# LED_board.net
KiCad netlist of a schematic drawn in EAGLE
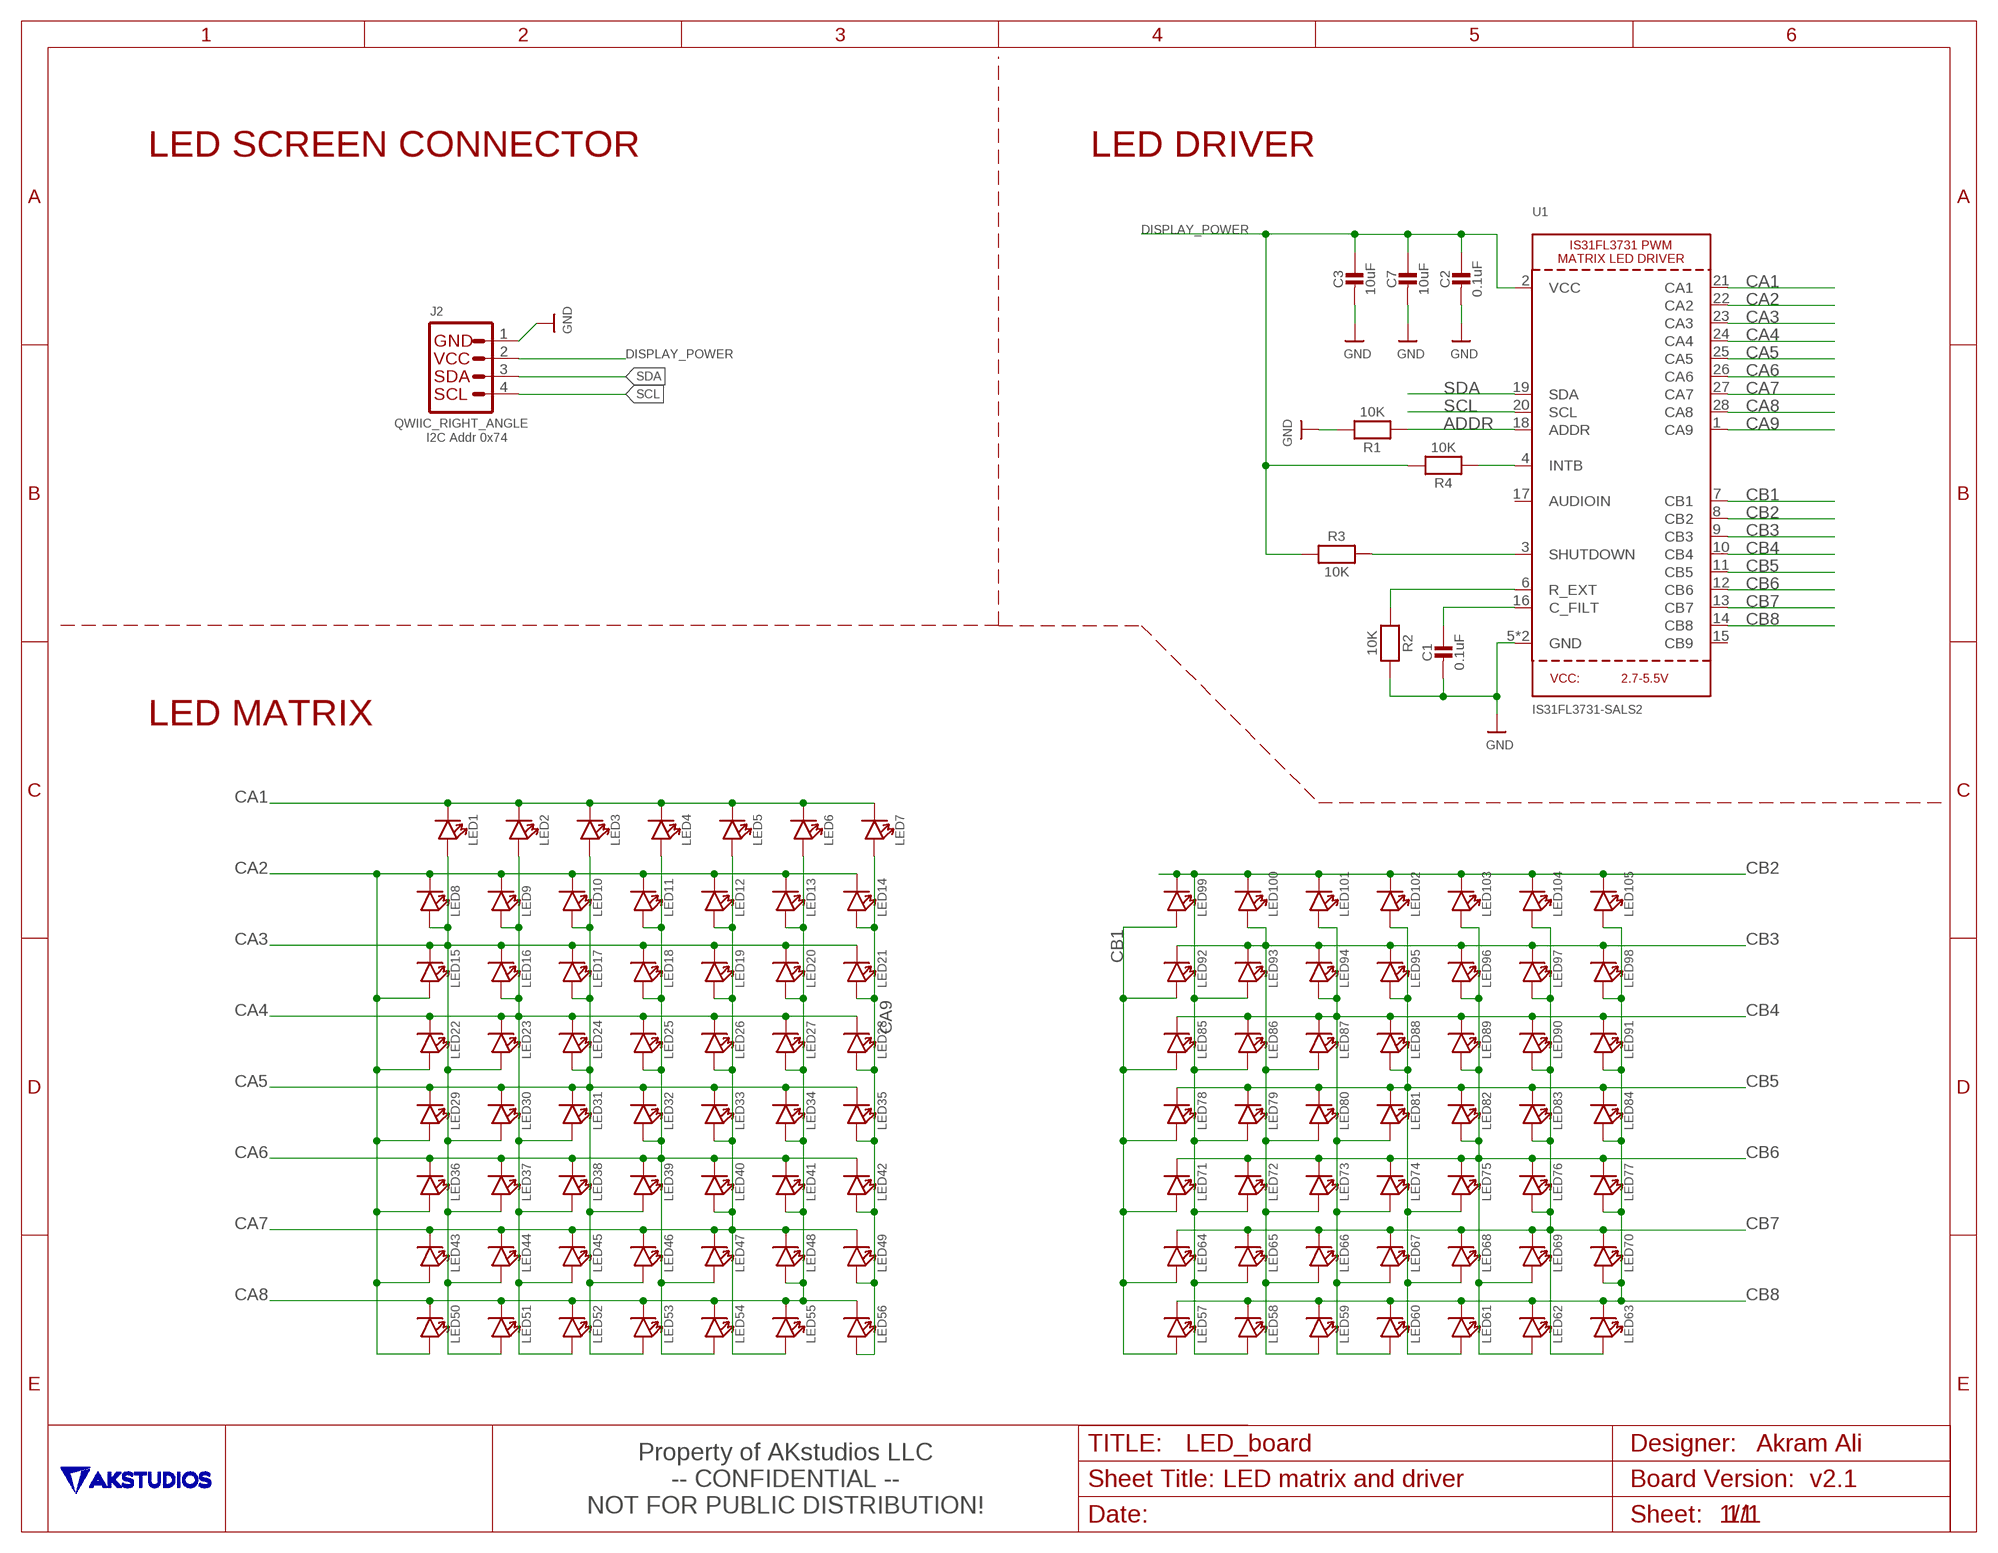
[diagram p0: schematic, sheet 1]

(export (version "E")
  (design (tool "Eeschema 10.0.6"))
  (components
    (comp (ref "C1")
      (value "0.1uF")
      (footprint "eagle-import:MICROBUILDER__0402MP")
      (fields (field (name "MPN") "GRM155R71C104KA88J"))
      (libsource (lib "eagle-import") (part "MICROBUILDER_CAP_CERAMIC_0402MP"))
    )
    (comp (ref "C2")
      (value "0.1uF")
      (footprint "eagle-import:MICROBUILDER__0402MP")
      (fields (field (name "MPN") "GRM155R71C104KA88J"))
      (libsource (lib "eagle-import") (part "MICROBUILDER_CAP_CERAMIC_0402MP"))
    )
    (comp (ref "C3")
      (value "10uF")
      (footprint "eagle-import:MICROBUILDER__0402MP")
      (fields (field (name "MPN") "GRM155R71C104KA88J"))
      (libsource (lib "eagle-import") (part "MICROBUILDER_CAP_CERAMIC_0402MP"))
    )
    (comp (ref "C7")
      (value "10uF")
      (footprint "eagle-import:MICROBUILDER__0402MP")
      (fields (field (name "MPN") "GRM155R71C104KA88J"))
      (libsource (lib "eagle-import") (part "MICROBUILDER_CAP_CERAMIC_0402MP"))
    )
    (comp (ref "J2")
      (value "QWIIC_RIGHT_ANGLE")
      (footprint "eagle-import:JST04_1MM_RA")
      (fields (field (name "MPN") "SM04B-SRSS-TB(LF)(SN)"))
      (libsource (lib "eagle-import") (part "QWIIC_CONNECTORJS-1MM"))
    )
    (comp (ref "LED1")
      (value "SMD-LED-CLEAR-BLUE(0402)")
      (footprint "eagle-import:LED-0402")
      (fields (field (name "MPN") "BL-HB337A-AV-TRB") (field (name "MPN_1") "IN-S42ATUW"))
      (libsource (lib "eagle-import") (part "SMD-LED-CLEAR-BLUE(0402)"))
    )
    (comp (ref "LED2")
      (value "SMD-LED-CLEAR-BLUE(0402)")
      (footprint "eagle-import:LED-0402")
      (fields (field (name "MPN") "BL-HB337A-AV-TRB") (field (name "MPN_1") "IN-S42ATUW"))
      (libsource (lib "eagle-import") (part "SMD-LED-CLEAR-BLUE(0402)"))
    )
    (comp (ref "LED3")
      (value "SMD-LED-CLEAR-BLUE(0402)")
      (footprint "eagle-import:LED-0402")
      (fields (field (name "MPN") "BL-HB337A-AV-TRB") (field (name "MPN_1") "IN-S42ATUW"))
      (libsource (lib "eagle-import") (part "SMD-LED-CLEAR-BLUE(0402)"))
    )
    (comp (ref "LED4")
      (value "SMD-LED-CLEAR-BLUE(0402)")
      (footprint "eagle-import:LED-0402")
      (fields (field (name "MPN") "BL-HB337A-AV-TRB") (field (name "MPN_1") "IN-S42ATUW"))
      (libsource (lib "eagle-import") (part "SMD-LED-CLEAR-BLUE(0402)"))
    )
    (comp (ref "LED5")
      (value "SMD-LED-CLEAR-BLUE(0402)")
      (footprint "eagle-import:LED-0402")
      (fields (field (name "MPN") "BL-HB337A-AV-TRB") (field (name "MPN_1") "IN-S42ATUW"))
      (libsource (lib "eagle-import") (part "SMD-LED-CLEAR-BLUE(0402)"))
    )
    (comp (ref "LED6")
      (value "SMD-LED-CLEAR-BLUE(0402)")
      (footprint "eagle-import:LED-0402")
      (fields (field (name "MPN") "BL-HB337A-AV-TRB") (field (name "MPN_1") "IN-S42ATUW"))
      (libsource (lib "eagle-import") (part "SMD-LED-CLEAR-BLUE(0402)"))
    )
    (comp (ref "LED7")
      (value "SMD-LED-CLEAR-BLUE(0402)")
      (footprint "eagle-import:LED-0402")
      (fields (field (name "MPN") "BL-HB337A-AV-TRB") (field (name "MPN_1") "IN-S42ATUW"))
      (libsource (lib "eagle-import") (part "SMD-LED-CLEAR-BLUE(0402)"))
    )
    (comp (ref "LED8")
      (value "SMD-LED-CLEAR-BLUE(0402)")
      (footprint "eagle-import:LED-0402")
      (fields (field (name "MPN") "BL-HB337A-AV-TRB") (field (name "MPN_1") "IN-S42ATUW"))
      (libsource (lib "eagle-import") (part "SMD-LED-CLEAR-BLUE(0402)"))
    )
    (comp (ref "LED9")
      (value "SMD-LED-CLEAR-BLUE(0402)")
      (footprint "eagle-import:LED-0402")
      (fields (field (name "MPN") "BL-HB337A-AV-TRB") (field (name "MPN_1") "IN-S42ATUW"))
      (libsource (lib "eagle-import") (part "SMD-LED-CLEAR-BLUE(0402)"))
    )
    (comp (ref "LED10")
      (value "SMD-LED-CLEAR-BLUE(0402)")
      (footprint "eagle-import:LED-0402")
      (fields (field (name "MPN") "BL-HB337A-AV-TRB") (field (name "MPN_1") "IN-S42ATUW"))
      (libsource (lib "eagle-import") (part "SMD-LED-CLEAR-BLUE(0402)"))
    )
    (comp (ref "LED11")
      (value "SMD-LED-CLEAR-BLUE(0402)")
      (footprint "eagle-import:LED-0402")
      (fields (field (name "MPN") "BL-HB337A-AV-TRB") (field (name "MPN_1") "IN-S42ATUW"))
      (libsource (lib "eagle-import") (part "SMD-LED-CLEAR-BLUE(0402)"))
    )
    (comp (ref "LED12")
      (value "SMD-LED-CLEAR-BLUE(0402)")
      (footprint "eagle-import:LED-0402")
      (fields (field (name "MPN") "BL-HB337A-AV-TRB") (field (name "MPN_1") "IN-S42ATUW"))
      (libsource (lib "eagle-import") (part "SMD-LED-CLEAR-BLUE(0402)"))
    )
    (comp (ref "LED13")
      (value "SMD-LED-CLEAR-BLUE(0402)")
      (footprint "eagle-import:LED-0402")
      (fields (field (name "MPN") "BL-HB337A-AV-TRB") (field (name "MPN_1") "IN-S42ATUW"))
      (libsource (lib "eagle-import") (part "SMD-LED-CLEAR-BLUE(0402)"))
    )
    (comp (ref "LED14")
      (value "SMD-LED-CLEAR-BLUE(0402)")
      (footprint "eagle-import:LED-0402")
      (fields (field (name "MPN") "BL-HB337A-AV-TRB") (field (name "MPN_1") "IN-S42ATUW"))
      (libsource (lib "eagle-import") (part "SMD-LED-CLEAR-BLUE(0402)"))
    )
    (comp (ref "LED15")
      (value "SMD-LED-CLEAR-BLUE(0402)")
      (footprint "eagle-import:LED-0402")
      (fields (field (name "MPN") "BL-HB337A-AV-TRB") (field (name "MPN_1") "IN-S42ATUW"))
      (libsource (lib "eagle-import") (part "SMD-LED-CLEAR-BLUE(0402)"))
    )
    (comp (ref "LED16")
      (value "SMD-LED-CLEAR-BLUE(0402)")
      (footprint "eagle-import:LED-0402")
      (fields (field (name "MPN") "BL-HB337A-AV-TRB") (field (name "MPN_1") "IN-S42ATUW"))
      (libsource (lib "eagle-import") (part "SMD-LED-CLEAR-BLUE(0402)"))
    )
    (comp (ref "LED17")
      (value "SMD-LED-CLEAR-BLUE(0402)")
      (footprint "eagle-import:LED-0402")
      (fields (field (name "MPN") "BL-HB337A-AV-TRB") (field (name "MPN_1") "IN-S42ATUW"))
      (libsource (lib "eagle-import") (part "SMD-LED-CLEAR-BLUE(0402)"))
    )
    (comp (ref "LED18")
      (value "SMD-LED-CLEAR-BLUE(0402)")
      (footprint "eagle-import:LED-0402")
      (fields (field (name "MPN") "BL-HB337A-AV-TRB") (field (name "MPN_1") "IN-S42ATUW"))
      (libsource (lib "eagle-import") (part "SMD-LED-CLEAR-BLUE(0402)"))
    )
    (comp (ref "LED19")
      (value "SMD-LED-CLEAR-BLUE(0402)")
      (footprint "eagle-import:LED-0402")
      (fields (field (name "MPN") "BL-HB337A-AV-TRB") (field (name "MPN_1") "IN-S42ATUW"))
      (libsource (lib "eagle-import") (part "SMD-LED-CLEAR-BLUE(0402)"))
    )
    (comp (ref "LED20")
      (value "SMD-LED-CLEAR-BLUE(0402)")
      (footprint "eagle-import:LED-0402")
      (fields (field (name "MPN") "BL-HB337A-AV-TRB") (field (name "MPN_1") "IN-S42ATUW"))
      (libsource (lib "eagle-import") (part "SMD-LED-CLEAR-BLUE(0402)"))
    )
    (comp (ref "LED21")
      (value "SMD-LED-CLEAR-BLUE(0402)")
      (footprint "eagle-import:LED-0402")
      (fields (field (name "MPN") "BL-HB337A-AV-TRB") (field (name "MPN_1") "IN-S42ATUW"))
      (libsource (lib "eagle-import") (part "SMD-LED-CLEAR-BLUE(0402)"))
    )
    (comp (ref "LED22")
      (value "SMD-LED-CLEAR-BLUE(0402)")
      (footprint "eagle-import:LED-0402")
      (fields (field (name "MPN") "BL-HB337A-AV-TRB") (field (name "MPN_1") "IN-S42ATUW"))
      (libsource (lib "eagle-import") (part "SMD-LED-CLEAR-BLUE(0402)"))
    )
    (comp (ref "LED23")
      (value "SMD-LED-CLEAR-BLUE(0402)")
      (footprint "eagle-import:LED-0402")
      (fields (field (name "MPN") "BL-HB337A-AV-TRB") (field (name "MPN_1") "IN-S42ATUW"))
      (libsource (lib "eagle-import") (part "SMD-LED-CLEAR-BLUE(0402)"))
    )
    (comp (ref "LED24")
      (value "SMD-LED-CLEAR-BLUE(0402)")
      (footprint "eagle-import:LED-0402")
      (fields (field (name "MPN") "BL-HB337A-AV-TRB") (field (name "MPN_1") "IN-S42ATUW"))
      (libsource (lib "eagle-import") (part "SMD-LED-CLEAR-BLUE(0402)"))
    )
    (comp (ref "LED25")
      (value "SMD-LED-CLEAR-BLUE(0402)")
      (footprint "eagle-import:LED-0402")
      (fields (field (name "MPN") "BL-HB337A-AV-TRB") (field (name "MPN_1") "IN-S42ATUW"))
      (libsource (lib "eagle-import") (part "SMD-LED-CLEAR-BLUE(0402)"))
    )
    (comp (ref "LED26")
      (value "SMD-LED-CLEAR-BLUE(0402)")
      (footprint "eagle-import:LED-0402")
      (fields (field (name "MPN") "BL-HB337A-AV-TRB") (field (name "MPN_1") "IN-S42ATUW"))
      (libsource (lib "eagle-import") (part "SMD-LED-CLEAR-BLUE(0402)"))
    )
    (comp (ref "LED27")
      (value "SMD-LED-CLEAR-BLUE(0402)")
      (footprint "eagle-import:LED-0402")
      (fields (field (name "MPN") "BL-HB337A-AV-TRB") (field (name "MPN_1") "IN-S42ATUW"))
      (libsource (lib "eagle-import") (part "SMD-LED-CLEAR-BLUE(0402)"))
    )
    (comp (ref "LED28")
      (value "SMD-LED-CLEAR-BLUE(0402)")
      (footprint "eagle-import:LED-0402")
      (fields (field (name "MPN") "BL-HB337A-AV-TRB") (field (name "MPN_1") "IN-S42ATUW"))
      (libsource (lib "eagle-import") (part "SMD-LED-CLEAR-BLUE(0402)"))
    )
    (comp (ref "LED29")
      (value "SMD-LED-CLEAR-BLUE(0402)")
      (footprint "eagle-import:LED-0402")
      (fields (field (name "MPN") "BL-HB337A-AV-TRB") (field (name "MPN_1") "IN-S42ATUW"))
      (libsource (lib "eagle-import") (part "SMD-LED-CLEAR-BLUE(0402)"))
    )
    (comp (ref "LED30")
      (value "SMD-LED-CLEAR-BLUE(0402)")
      (footprint "eagle-import:LED-0402")
      (fields (field (name "MPN") "BL-HB337A-AV-TRB") (field (name "MPN_1") "IN-S42ATUW"))
      (libsource (lib "eagle-import") (part "SMD-LED-CLEAR-BLUE(0402)"))
    )
    (comp (ref "LED31")
      (value "SMD-LED-CLEAR-BLUE(0402)")
      (footprint "eagle-import:LED-0402")
      (fields (field (name "MPN") "BL-HB337A-AV-TRB") (field (name "MPN_1") "IN-S42ATUW"))
      (libsource (lib "eagle-import") (part "SMD-LED-CLEAR-BLUE(0402)"))
    )
    (comp (ref "LED32")
      (value "SMD-LED-CLEAR-BLUE(0402)")
      (footprint "eagle-import:LED-0402")
      (fields (field (name "MPN") "BL-HB337A-AV-TRB") (field (name "MPN_1") "IN-S42ATUW"))
      (libsource (lib "eagle-import") (part "SMD-LED-CLEAR-BLUE(0402)"))
    )
    (comp (ref "LED33")
      (value "SMD-LED-CLEAR-BLUE(0402)")
      (footprint "eagle-import:LED-0402")
      (fields (field (name "MPN") "BL-HB337A-AV-TRB") (field (name "MPN_1") "IN-S42ATUW"))
      (libsource (lib "eagle-import") (part "SMD-LED-CLEAR-BLUE(0402)"))
    )
    (comp (ref "LED34")
      (value "SMD-LED-CLEAR-BLUE(0402)")
      (footprint "eagle-import:LED-0402")
      (fields (field (name "MPN") "BL-HB337A-AV-TRB") (field (name "MPN_1") "IN-S42ATUW"))
      (libsource (lib "eagle-import") (part "SMD-LED-CLEAR-BLUE(0402)"))
    )
    (comp (ref "LED35")
      (value "SMD-LED-CLEAR-BLUE(0402)")
      (footprint "eagle-import:LED-0402")
      (fields (field (name "MPN") "BL-HB337A-AV-TRB") (field (name "MPN_1") "IN-S42ATUW"))
      (libsource (lib "eagle-import") (part "SMD-LED-CLEAR-BLUE(0402)"))
    )
    (comp (ref "LED36")
      (value "SMD-LED-CLEAR-BLUE(0402)")
      (footprint "eagle-import:LED-0402")
      (fields (field (name "MPN") "BL-HB337A-AV-TRB") (field (name "MPN_1") "IN-S42ATUW"))
      (libsource (lib "eagle-import") (part "SMD-LED-CLEAR-BLUE(0402)"))
    )
    (comp (ref "LED37")
      (value "SMD-LED-CLEAR-BLUE(0402)")
      (footprint "eagle-import:LED-0402")
      (fields (field (name "MPN") "BL-HB337A-AV-TRB") (field (name "MPN_1") "IN-S42ATUW"))
      (libsource (lib "eagle-import") (part "SMD-LED-CLEAR-BLUE(0402)"))
    )
    (comp (ref "LED38")
      (value "SMD-LED-CLEAR-BLUE(0402)")
      (footprint "eagle-import:LED-0402")
      (fields (field (name "MPN") "BL-HB337A-AV-TRB") (field (name "MPN_1") "IN-S42ATUW"))
      (libsource (lib "eagle-import") (part "SMD-LED-CLEAR-BLUE(0402)"))
    )
    (comp (ref "LED39")
      (value "SMD-LED-CLEAR-BLUE(0402)")
      (footprint "eagle-import:LED-0402")
      (fields (field (name "MPN") "BL-HB337A-AV-TRB") (field (name "MPN_1") "IN-S42ATUW"))
      (libsource (lib "eagle-import") (part "SMD-LED-CLEAR-BLUE(0402)"))
    )
    (comp (ref "LED40")
      (value "SMD-LED-CLEAR-BLUE(0402)")
      (footprint "eagle-import:LED-0402")
      (fields (field (name "MPN") "BL-HB337A-AV-TRB") (field (name "MPN_1") "IN-S42ATUW"))
      (libsource (lib "eagle-import") (part "SMD-LED-CLEAR-BLUE(0402)"))
    )
    (comp (ref "LED41")
      (value "SMD-LED-CLEAR-BLUE(0402)")
      (footprint "eagle-import:LED-0402")
      (fields (field (name "MPN") "BL-HB337A-AV-TRB") (field (name "MPN_1") "IN-S42ATUW"))
      (libsource (lib "eagle-import") (part "SMD-LED-CLEAR-BLUE(0402)"))
    )
    (comp (ref "LED42")
      (value "SMD-LED-CLEAR-BLUE(0402)")
      (footprint "eagle-import:LED-0402")
      (fields (field (name "MPN") "BL-HB337A-AV-TRB") (field (name "MPN_1") "IN-S42ATUW"))
      (libsource (lib "eagle-import") (part "SMD-LED-CLEAR-BLUE(0402)"))
    )
    (comp (ref "LED43")
      (value "SMD-LED-CLEAR-BLUE(0402)")
      (footprint "eagle-import:LED-0402")
      (fields (field (name "MPN") "BL-HB337A-AV-TRB") (field (name "MPN_1") "IN-S42ATUW"))
      (libsource (lib "eagle-import") (part "SMD-LED-CLEAR-BLUE(0402)"))
    )
    (comp (ref "LED44")
      (value "SMD-LED-CLEAR-BLUE(0402)")
      (footprint "eagle-import:LED-0402")
      (fields (field (name "MPN") "BL-HB337A-AV-TRB") (field (name "MPN_1") "IN-S42ATUW"))
      (libsource (lib "eagle-import") (part "SMD-LED-CLEAR-BLUE(0402)"))
    )
    (comp (ref "LED45")
      (value "SMD-LED-CLEAR-BLUE(0402)")
      (footprint "eagle-import:LED-0402")
      (fields (field (name "MPN") "BL-HB337A-AV-TRB") (field (name "MPN_1") "IN-S42ATUW"))
      (libsource (lib "eagle-import") (part "SMD-LED-CLEAR-BLUE(0402)"))
    )
    (comp (ref "LED46")
      (value "SMD-LED-CLEAR-BLUE(0402)")
      (footprint "eagle-import:LED-0402")
      (fields (field (name "MPN") "BL-HB337A-AV-TRB") (field (name "MPN_1") "IN-S42ATUW"))
      (libsource (lib "eagle-import") (part "SMD-LED-CLEAR-BLUE(0402)"))
    )
    (comp (ref "LED47")
      (value "SMD-LED-CLEAR-BLUE(0402)")
      (footprint "eagle-import:LED-0402")
      (fields (field (name "MPN") "BL-HB337A-AV-TRB") (field (name "MPN_1") "IN-S42ATUW"))
      (libsource (lib "eagle-import") (part "SMD-LED-CLEAR-BLUE(0402)"))
    )
    (comp (ref "LED48")
      (value "SMD-LED-CLEAR-BLUE(0402)")
      (footprint "eagle-import:LED-0402")
      (fields (field (name "MPN") "BL-HB337A-AV-TRB") (field (name "MPN_1") "IN-S42ATUW"))
      (libsource (lib "eagle-import") (part "SMD-LED-CLEAR-BLUE(0402)"))
    )
    (comp (ref "LED49")
      (value "SMD-LED-CLEAR-BLUE(0402)")
      (footprint "eagle-import:LED-0402")
      (fields (field (name "MPN") "BL-HB337A-AV-TRB") (field (name "MPN_1") "IN-S42ATUW"))
      (libsource (lib "eagle-import") (part "SMD-LED-CLEAR-BLUE(0402)"))
    )
    (comp (ref "LED50")
      (value "SMD-LED-CLEAR-BLUE(0402)")
      (footprint "eagle-import:LED-0402")
      (fields (field (name "MPN") "BL-HB337A-AV-TRB") (field (name "MPN_1") "IN-S42ATUW"))
      (libsource (lib "eagle-import") (part "SMD-LED-CLEAR-BLUE(0402)"))
    )
    (comp (ref "LED51")
      (value "SMD-LED-CLEAR-BLUE(0402)")
      (footprint "eagle-import:LED-0402")
      (fields (field (name "MPN") "BL-HB337A-AV-TRB") (field (name "MPN_1") "IN-S42ATUW"))
      (libsource (lib "eagle-import") (part "SMD-LED-CLEAR-BLUE(0402)"))
    )
    (comp (ref "LED52")
      (value "SMD-LED-CLEAR-BLUE(0402)")
      (footprint "eagle-import:LED-0402")
      (fields (field (name "MPN") "BL-HB337A-AV-TRB") (field (name "MPN_1") "IN-S42ATUW"))
      (libsource (lib "eagle-import") (part "SMD-LED-CLEAR-BLUE(0402)"))
    )
    (comp (ref "LED53")
      (value "SMD-LED-CLEAR-BLUE(0402)")
      (footprint "eagle-import:LED-0402")
      (fields (field (name "MPN") "BL-HB337A-AV-TRB") (field (name "MPN_1") "IN-S42ATUW"))
      (libsource (lib "eagle-import") (part "SMD-LED-CLEAR-BLUE(0402)"))
    )
    (comp (ref "LED54")
      (value "SMD-LED-CLEAR-BLUE(0402)")
      (footprint "eagle-import:LED-0402")
      (fields (field (name "MPN") "BL-HB337A-AV-TRB") (field (name "MPN_1") "IN-S42ATUW"))
      (libsource (lib "eagle-import") (part "SMD-LED-CLEAR-BLUE(0402)"))
    )
    (comp (ref "LED55")
      (value "SMD-LED-CLEAR-BLUE(0402)")
      (footprint "eagle-import:LED-0402")
      (fields (field (name "MPN") "BL-HB337A-AV-TRB") (field (name "MPN_1") "IN-S42ATUW"))
      (libsource (lib "eagle-import") (part "SMD-LED-CLEAR-BLUE(0402)"))
    )
    (comp (ref "LED56")
      (value "SMD-LED-CLEAR-BLUE(0402)")
      (footprint "eagle-import:LED-0402")
      (fields (field (name "MPN") "BL-HB337A-AV-TRB") (field (name "MPN_1") "IN-S42ATUW"))
      (libsource (lib "eagle-import") (part "SMD-LED-CLEAR-BLUE(0402)"))
    )
    (comp (ref "LED57")
      (value "SMD-LED-CLEAR-BLUE(0402)")
      (footprint "eagle-import:LED-0402")
      (fields (field (name "MPN") "BL-HB337A-AV-TRB") (field (name "MPN_1") "IN-S42ATUW"))
      (libsource (lib "eagle-import") (part "SMD-LED-CLEAR-BLUE(0402)"))
    )
    (comp (ref "LED58")
      (value "SMD-LED-CLEAR-BLUE(0402)")
      (footprint "eagle-import:LED-0402")
      (fields (field (name "MPN") "BL-HB337A-AV-TRB") (field (name "MPN_1") "IN-S42ATUW"))
      (libsource (lib "eagle-import") (part "SMD-LED-CLEAR-BLUE(0402)"))
    )
    (comp (ref "LED59")
      (value "SMD-LED-CLEAR-BLUE(0402)")
      (footprint "eagle-import:LED-0402")
      (fields (field (name "MPN") "BL-HB337A-AV-TRB") (field (name "MPN_1") "IN-S42ATUW"))
      (libsource (lib "eagle-import") (part "SMD-LED-CLEAR-BLUE(0402)"))
    )
    (comp (ref "LED60")
      (value "SMD-LED-CLEAR-BLUE(0402)")
      (footprint "eagle-import:LED-0402")
      (fields (field (name "MPN") "BL-HB337A-AV-TRB") (field (name "MPN_1") "IN-S42ATUW"))
      (libsource (lib "eagle-import") (part "SMD-LED-CLEAR-BLUE(0402)"))
    )
    (comp (ref "LED61")
      (value "SMD-LED-CLEAR-BLUE(0402)")
      (footprint "eagle-import:LED-0402")
      (fields (field (name "MPN") "BL-HB337A-AV-TRB") (field (name "MPN_1") "IN-S42ATUW"))
      (libsource (lib "eagle-import") (part "SMD-LED-CLEAR-BLUE(0402)"))
    )
    (comp (ref "LED62")
      (value "SMD-LED-CLEAR-BLUE(0402)")
      (footprint "eagle-import:LED-0402")
      (fields (field (name "MPN") "BL-HB337A-AV-TRB") (field (name "MPN_1") "IN-S42ATUW"))
      (libsource (lib "eagle-import") (part "SMD-LED-CLEAR-BLUE(0402)"))
    )
    (comp (ref "LED63")
      (value "SMD-LED-CLEAR-BLUE(0402)")
      (footprint "eagle-import:LED-0402")
      (fields (field (name "MPN") "BL-HB337A-AV-TRB") (field (name "MPN_1") "IN-S42ATUW"))
      (libsource (lib "eagle-import") (part "SMD-LED-CLEAR-BLUE(0402)"))
    )
    (comp (ref "LED64")
      (value "SMD-LED-CLEAR-BLUE(0402)")
      (footprint "eagle-import:LED-0402")
      (fields (field (name "MPN") "BL-HB337A-AV-TRB") (field (name "MPN_1") "IN-S42ATUW"))
      (libsource (lib "eagle-import") (part "SMD-LED-CLEAR-BLUE(0402)"))
    )
    (comp (ref "LED65")
      (value "SMD-LED-CLEAR-BLUE(0402)")
      (footprint "eagle-import:LED-0402")
      (fields (field (name "MPN") "BL-HB337A-AV-TRB") (field (name "MPN_1") "IN-S42ATUW"))
      (libsource (lib "eagle-import") (part "SMD-LED-CLEAR-BLUE(0402)"))
    )
    (comp (ref "LED66")
      (value "SMD-LED-CLEAR-BLUE(0402)")
      (footprint "eagle-import:LED-0402")
      (fields (field (name "MPN") "BL-HB337A-AV-TRB") (field (name "MPN_1") "IN-S42ATUW"))
      (libsource (lib "eagle-import") (part "SMD-LED-CLEAR-BLUE(0402)"))
    )
    (comp (ref "LED67")
      (value "SMD-LED-CLEAR-BLUE(0402)")
      (footprint "eagle-import:LED-0402")
      (fields (field (name "MPN") "BL-HB337A-AV-TRB") (field (name "MPN_1") "IN-S42ATUW"))
      (libsource (lib "eagle-import") (part "SMD-LED-CLEAR-BLUE(0402)"))
    )
    (comp (ref "LED68")
      (value "SMD-LED-CLEAR-BLUE(0402)")
      (footprint "eagle-import:LED-0402")
      (fields (field (name "MPN") "BL-HB337A-AV-TRB") (field (name "MPN_1") "IN-S42ATUW"))
      (libsource (lib "eagle-import") (part "SMD-LED-CLEAR-BLUE(0402)"))
    )
    (comp (ref "LED69")
      (value "SMD-LED-CLEAR-BLUE(0402)")
      (footprint "eagle-import:LED-0402")
      (fields (field (name "MPN") "BL-HB337A-AV-TRB") (field (name "MPN_1") "IN-S42ATUW"))
      (libsource (lib "eagle-import") (part "SMD-LED-CLEAR-BLUE(0402)"))
    )
    (comp (ref "LED70")
      (value "SMD-LED-CLEAR-BLUE(0402)")
      (footprint "eagle-import:LED-0402")
      (fields (field (name "MPN") "BL-HB337A-AV-TRB") (field (name "MPN_1") "IN-S42ATUW"))
      (libsource (lib "eagle-import") (part "SMD-LED-CLEAR-BLUE(0402)"))
    )
    (comp (ref "LED71")
      (value "SMD-LED-CLEAR-BLUE(0402)")
      (footprint "eagle-import:LED-0402")
      (fields (field (name "MPN") "BL-HB337A-AV-TRB") (field (name "MPN_1") "IN-S42ATUW"))
      (libsource (lib "eagle-import") (part "SMD-LED-CLEAR-BLUE(0402)"))
    )
    (comp (ref "LED72")
      (value "SMD-LED-CLEAR-BLUE(0402)")
      (footprint "eagle-import:LED-0402")
      (fields (field (name "MPN") "BL-HB337A-AV-TRB") (field (name "MPN_1") "IN-S42ATUW"))
      (libsource (lib "eagle-import") (part "SMD-LED-CLEAR-BLUE(0402)"))
    )
    (comp (ref "LED73")
      (value "SMD-LED-CLEAR-BLUE(0402)")
      (footprint "eagle-import:LED-0402")
      (fields (field (name "MPN") "BL-HB337A-AV-TRB") (field (name "MPN_1") "IN-S42ATUW"))
      (libsource (lib "eagle-import") (part "SMD-LED-CLEAR-BLUE(0402)"))
    )
    (comp (ref "LED74")
      (value "SMD-LED-CLEAR-BLUE(0402)")
      (footprint "eagle-import:LED-0402")
      (fields (field (name "MPN") "BL-HB337A-AV-TRB") (field (name "MPN_1") "IN-S42ATUW"))
      (libsource (lib "eagle-import") (part "SMD-LED-CLEAR-BLUE(0402)"))
    )
    (comp (ref "LED75")
      (value "SMD-LED-CLEAR-BLUE(0402)")
      (footprint "eagle-import:LED-0402")
      (fields (field (name "MPN") "BL-HB337A-AV-TRB") (field (name "MPN_1") "IN-S42ATUW"))
      (libsource (lib "eagle-import") (part "SMD-LED-CLEAR-BLUE(0402)"))
    )
    (comp (ref "LED76")
      (value "SMD-LED-CLEAR-BLUE(0402)")
      (footprint "eagle-import:LED-0402")
      (fields (field (name "MPN") "BL-HB337A-AV-TRB") (field (name "MPN_1") "IN-S42ATUW"))
      (libsource (lib "eagle-import") (part "SMD-LED-CLEAR-BLUE(0402)"))
    )
    (comp (ref "LED77")
      (value "SMD-LED-CLEAR-BLUE(0402)")
      (footprint "eagle-import:LED-0402")
      (fields (field (name "MPN") "BL-HB337A-AV-TRB") (field (name "MPN_1") "IN-S42ATUW"))
      (libsource (lib "eagle-import") (part "SMD-LED-CLEAR-BLUE(0402)"))
    )
    (comp (ref "LED78")
      (value "SMD-LED-CLEAR-BLUE(0402)")
      (footprint "eagle-import:LED-0402")
      (fields (field (name "MPN") "BL-HB337A-AV-TRB") (field (name "MPN_1") "IN-S42ATUW"))
      (libsource (lib "eagle-import") (part "SMD-LED-CLEAR-BLUE(0402)"))
    )
    (comp (ref "LED79")
      (value "SMD-LED-CLEAR-BLUE(0402)")
      (footprint "eagle-import:LED-0402")
      (fields (field (name "MPN") "BL-HB337A-AV-TRB") (field (name "MPN_1") "IN-S42ATUW"))
      (libsource (lib "eagle-import") (part "SMD-LED-CLEAR-BLUE(0402)"))
    )
    (comp (ref "LED80")
      (value "SMD-LED-CLEAR-BLUE(0402)")
      (footprint "eagle-import:LED-0402")
      (fields (field (name "MPN") "BL-HB337A-AV-TRB") (field (name "MPN_1") "IN-S42ATUW"))
      (libsource (lib "eagle-import") (part "SMD-LED-CLEAR-BLUE(0402)"))
    )
    (comp (ref "LED81")
      (value "SMD-LED-CLEAR-BLUE(0402)")
      (footprint "eagle-import:LED-0402")
      (fields (field (name "MPN") "BL-HB337A-AV-TRB") (field (name "MPN_1") "IN-S42ATUW"))
      (libsource (lib "eagle-import") (part "SMD-LED-CLEAR-BLUE(0402)"))
    )
    (comp (ref "LED82")
      (value "SMD-LED-CLEAR-BLUE(0402)")
      (footprint "eagle-import:LED-0402")
      (fields (field (name "MPN") "BL-HB337A-AV-TRB") (field (name "MPN_1") "IN-S42ATUW"))
      (libsource (lib "eagle-import") (part "SMD-LED-CLEAR-BLUE(0402)"))
    )
    (comp (ref "LED83")
      (value "SMD-LED-CLEAR-BLUE(0402)")
      (footprint "eagle-import:LED-0402")
      (fields (field (name "MPN") "BL-HB337A-AV-TRB") (field (name "MPN_1") "IN-S42ATUW"))
      (libsource (lib "eagle-import") (part "SMD-LED-CLEAR-BLUE(0402)"))
    )
    (comp (ref "LED84")
      (value "SMD-LED-CLEAR-BLUE(0402)")
      (footprint "eagle-import:LED-0402")
      (fields (field (name "MPN") "BL-HB337A-AV-TRB") (field (name "MPN_1") "IN-S42ATUW"))
      (libsource (lib "eagle-import") (part "SMD-LED-CLEAR-BLUE(0402)"))
    )
    (comp (ref "LED85")
      (value "SMD-LED-CLEAR-BLUE(0402)")
      (footprint "eagle-import:LED-0402")
      (fields (field (name "MPN") "BL-HB337A-AV-TRB") (field (name "MPN_1") "IN-S42ATUW"))
      (libsource (lib "eagle-import") (part "SMD-LED-CLEAR-BLUE(0402)"))
    )
    (comp (ref "LED86")
      (value "SMD-LED-CLEAR-BLUE(0402)")
      (footprint "eagle-import:LED-0402")
      (fields (field (name "MPN") "BL-HB337A-AV-TRB") (field (name "MPN_1") "IN-S42ATUW"))
      (libsource (lib "eagle-import") (part "SMD-LED-CLEAR-BLUE(0402)"))
    )
    (comp (ref "LED87")
      (value "SMD-LED-CLEAR-BLUE(0402)")
      (footprint "eagle-import:LED-0402")
      (fields (field (name "MPN") "BL-HB337A-AV-TRB") (field (name "MPN_1") "IN-S42ATUW"))
      (libsource (lib "eagle-import") (part "SMD-LED-CLEAR-BLUE(0402)"))
    )
    (comp (ref "LED88")
      (value "SMD-LED-CLEAR-BLUE(0402)")
      (footprint "eagle-import:LED-0402")
      (fields (field (name "MPN") "BL-HB337A-AV-TRB") (field (name "MPN_1") "IN-S42ATUW"))
      (libsource (lib "eagle-import") (part "SMD-LED-CLEAR-BLUE(0402)"))
    )
    (comp (ref "LED89")
      (value "SMD-LED-CLEAR-BLUE(0402)")
      (footprint "eagle-import:LED-0402")
      (fields (field (name "MPN") "BL-HB337A-AV-TRB") (field (name "MPN_1") "IN-S42ATUW"))
      (libsource (lib "eagle-import") (part "SMD-LED-CLEAR-BLUE(0402)"))
    )
    (comp (ref "LED90")
      (value "SMD-LED-CLEAR-BLUE(0402)")
      (footprint "eagle-import:LED-0402")
      (fields (field (name "MPN") "BL-HB337A-AV-TRB") (field (name "MPN_1") "IN-S42ATUW"))
      (libsource (lib "eagle-import") (part "SMD-LED-CLEAR-BLUE(0402)"))
    )
    (comp (ref "LED91")
      (value "SMD-LED-CLEAR-BLUE(0402)")
      (footprint "eagle-import:LED-0402")
      (fields (field (name "MPN") "BL-HB337A-AV-TRB") (field (name "MPN_1") "IN-S42ATUW"))
      (libsource (lib "eagle-import") (part "SMD-LED-CLEAR-BLUE(0402)"))
    )
    (comp (ref "LED92")
      (value "SMD-LED-CLEAR-BLUE(0402)")
      (footprint "eagle-import:LED-0402")
      (fields (field (name "MPN") "BL-HB337A-AV-TRB") (field (name "MPN_1") "IN-S42ATUW"))
      (libsource (lib "eagle-import") (part "SMD-LED-CLEAR-BLUE(0402)"))
    )
    (comp (ref "LED93")
      (value "SMD-LED-CLEAR-BLUE(0402)")
      (footprint "eagle-import:LED-0402")
      (fields (field (name "MPN") "BL-HB337A-AV-TRB") (field (name "MPN_1") "IN-S42ATUW"))
      (libsource (lib "eagle-import") (part "SMD-LED-CLEAR-BLUE(0402)"))
    )
    (comp (ref "LED94")
      (value "SMD-LED-CLEAR-BLUE(0402)")
      (footprint "eagle-import:LED-0402")
      (fields (field (name "MPN") "BL-HB337A-AV-TRB") (field (name "MPN_1") "IN-S42ATUW"))
      (libsource (lib "eagle-import") (part "SMD-LED-CLEAR-BLUE(0402)"))
    )
    (comp (ref "LED95")
      (value "SMD-LED-CLEAR-BLUE(0402)")
      (footprint "eagle-import:LED-0402")
      (fields (field (name "MPN") "BL-HB337A-AV-TRB") (field (name "MPN_1") "IN-S42ATUW"))
      (libsource (lib "eagle-import") (part "SMD-LED-CLEAR-BLUE(0402)"))
    )
    (comp (ref "LED96")
      (value "SMD-LED-CLEAR-BLUE(0402)")
      (footprint "eagle-import:LED-0402")
      (fields (field (name "MPN") "BL-HB337A-AV-TRB") (field (name "MPN_1") "IN-S42ATUW"))
      (libsource (lib "eagle-import") (part "SMD-LED-CLEAR-BLUE(0402)"))
    )
    (comp (ref "LED97")
      (value "SMD-LED-CLEAR-BLUE(0402)")
      (footprint "eagle-import:LED-0402")
      (fields (field (name "MPN") "BL-HB337A-AV-TRB") (field (name "MPN_1") "IN-S42ATUW"))
      (libsource (lib "eagle-import") (part "SMD-LED-CLEAR-BLUE(0402)"))
    )
    (comp (ref "LED98")
      (value "SMD-LED-CLEAR-BLUE(0402)")
      (footprint "eagle-import:LED-0402")
      (fields (field (name "MPN") "BL-HB337A-AV-TRB") (field (name "MPN_1") "IN-S42ATUW"))
      (libsource (lib "eagle-import") (part "SMD-LED-CLEAR-BLUE(0402)"))
    )
    (comp (ref "LED99")
      (value "SMD-LED-CLEAR-BLUE(0402)")
      (footprint "eagle-import:LED-0402")
      (fields (field (name "MPN") "BL-HB337A-AV-TRB") (field (name "MPN_1") "IN-S42ATUW"))
      (libsource (lib "eagle-import") (part "SMD-LED-CLEAR-BLUE(0402)"))
    )
    (comp (ref "LED100")
      (value "SMD-LED-CLEAR-BLUE(0402)")
      (footprint "eagle-import:LED-0402")
      (fields (field (name "MPN") "BL-HB337A-AV-TRB") (field (name "MPN_1") "IN-S42ATUW"))
      (libsource (lib "eagle-import") (part "SMD-LED-CLEAR-BLUE(0402)"))
    )
    (comp (ref "LED101")
      (value "SMD-LED-CLEAR-BLUE(0402)")
      (footprint "eagle-import:LED-0402")
      (fields (field (name "MPN") "BL-HB337A-AV-TRB") (field (name "MPN_1") "IN-S42ATUW"))
      (libsource (lib "eagle-import") (part "SMD-LED-CLEAR-BLUE(0402)"))
    )
    (comp (ref "LED102")
      (value "SMD-LED-CLEAR-BLUE(0402)")
      (footprint "eagle-import:LED-0402")
      (fields (field (name "MPN") "BL-HB337A-AV-TRB") (field (name "MPN_1") "IN-S42ATUW"))
      (libsource (lib "eagle-import") (part "SMD-LED-CLEAR-BLUE(0402)"))
    )
    (comp (ref "LED103")
      (value "SMD-LED-CLEAR-BLUE(0402)")
      (footprint "eagle-import:LED-0402")
      (fields (field (name "MPN") "BL-HB337A-AV-TRB") (field (name "MPN_1") "IN-S42ATUW"))
      (libsource (lib "eagle-import") (part "SMD-LED-CLEAR-BLUE(0402)"))
    )
    (comp (ref "LED104")
      (value "SMD-LED-CLEAR-BLUE(0402)")
      (footprint "eagle-import:LED-0402")
      (fields (field (name "MPN") "BL-HB337A-AV-TRB") (field (name "MPN_1") "IN-S42ATUW"))
      (libsource (lib "eagle-import") (part "SMD-LED-CLEAR-BLUE(0402)"))
    )
    (comp (ref "LED105")
      (value "SMD-LED-CLEAR-BLUE(0402)")
      (footprint "eagle-import:LED-0402")
      (fields (field (name "MPN") "BL-HB337A-AV-TRB") (field (name "MPN_1") "IN-S42ATUW"))
      (libsource (lib "eagle-import") (part "SMD-LED-CLEAR-BLUE(0402)"))
    )
    (comp (ref "R1")
      (value "10K")
      (footprint "eagle-import:MICROBUILDER__0402MP")
      (fields (field (name "MPN") "RC0402FR-7W10KL"))
      (libsource (lib "eagle-import") (part "MICROBUILDER_RESISTOR_0402MP"))
    )
    (comp (ref "R2")
      (value "10K")
      (footprint "eagle-import:MICROBUILDER__0402MP")
      (fields (field (name "MPN") "RC0402FR-7W10KL"))
      (libsource (lib "eagle-import") (part "MICROBUILDER_RESISTOR_0402MP"))
    )
    (comp (ref "R3")
      (value "10K")
      (footprint "eagle-import:MICROBUILDER__0402MP")
      (fields (field (name "MPN") "RC0402FR-7W10KL"))
      (libsource (lib "eagle-import") (part "MICROBUILDER_RESISTOR_0402MP"))
    )
    (comp (ref "R4")
      (value "10K")
      (footprint "eagle-import:MICROBUILDER__0402MP")
      (fields (field (name "MPN") "RC0402FR-7W10KL"))
      (libsource (lib "eagle-import") (part "MICROBUILDER_RESISTOR_0402MP"))
    )
    (comp (ref "U1")
      (value "IS31FL3731-SALS2")
      (footprint "eagle-import:QFN28_4MM_0.4MM")
      (libsource (lib "eagle-import") (part "IS31FL3731QFN"))
    )
  )
  (nets
    (net (code "1") (name "/ADDR") (class "Default")
      (node (ref "R1") (pin "1") (pinfunction "1_1") (pintype "passive"))
      (node (ref "U1") (pin "18") (pinfunction "ADDR_18") (pintype "bidirectional"))
    )
    (net (code "2") (name "/CA1") (class "Default")
      (node (ref "LED1") (pin "-") (pinfunction "-_-") (pintype "passive"))
      (node (ref "LED2") (pin "-") (pinfunction "-_-") (pintype "passive"))
      (node (ref "LED3") (pin "-") (pinfunction "-_-") (pintype "passive"))
      (node (ref "LED4") (pin "-") (pinfunction "-_-") (pintype "passive"))
      (node (ref "LED5") (pin "-") (pinfunction "-_-") (pintype "passive"))
      (node (ref "LED6") (pin "-") (pinfunction "-_-") (pintype "passive"))
      (node (ref "LED7") (pin "-") (pinfunction "-_-") (pintype "passive"))
      (node (ref "U1") (pin "21") (pinfunction "CA1_21") (pintype "bidirectional"))
    )
    (net (code "3") (name "/CA2") (class "Default")
      (node (ref "LED10") (pin "-") (pinfunction "-_-") (pintype "passive"))
      (node (ref "LED11") (pin "-") (pinfunction "-_-") (pintype "passive"))
      (node (ref "LED12") (pin "-") (pinfunction "-_-") (pintype "passive"))
      (node (ref "LED13") (pin "-") (pinfunction "-_-") (pintype "passive"))
      (node (ref "LED14") (pin "-") (pinfunction "-_-") (pintype "passive"))
      (node (ref "LED15") (pin "+") (pinfunction "+_+") (pintype "passive"))
      (node (ref "LED22") (pin "+") (pinfunction "+_+") (pintype "passive"))
      (node (ref "LED29") (pin "+") (pinfunction "+_+") (pintype "passive"))
      (node (ref "LED36") (pin "+") (pinfunction "+_+") (pintype "passive"))
      (node (ref "LED43") (pin "+") (pinfunction "+_+") (pintype "passive"))
      (node (ref "LED50") (pin "+") (pinfunction "+_+") (pintype "passive"))
      (node (ref "LED8") (pin "-") (pinfunction "-_-") (pintype "passive"))
      (node (ref "LED9") (pin "-") (pinfunction "-_-") (pintype "passive"))
      (node (ref "U1") (pin "22") (pinfunction "CA2_22") (pintype "bidirectional"))
    )
    (net (code "4") (name "/CA3") (class "Default")
      (node (ref "LED1") (pin "+") (pinfunction "+_+") (pintype "passive"))
      (node (ref "LED15") (pin "-") (pinfunction "-_-") (pintype "passive"))
      (node (ref "LED16") (pin "-") (pinfunction "-_-") (pintype "passive"))
      (node (ref "LED17") (pin "-") (pinfunction "-_-") (pintype "passive"))
      (node (ref "LED18") (pin "-") (pinfunction "-_-") (pintype "passive"))
      (node (ref "LED19") (pin "-") (pinfunction "-_-") (pintype "passive"))
      (node (ref "LED20") (pin "-") (pinfunction "-_-") (pintype "passive"))
      (node (ref "LED21") (pin "-") (pinfunction "-_-") (pintype "passive"))
      (node (ref "LED23") (pin "+") (pinfunction "+_+") (pintype "passive"))
      (node (ref "LED30") (pin "+") (pinfunction "+_+") (pintype "passive"))
      (node (ref "LED37") (pin "+") (pinfunction "+_+") (pintype "passive"))
      (node (ref "LED44") (pin "+") (pinfunction "+_+") (pintype "passive"))
      (node (ref "LED51") (pin "+") (pinfunction "+_+") (pintype "passive"))
      (node (ref "LED8") (pin "+") (pinfunction "+_+") (pintype "passive"))
      (node (ref "U1") (pin "23") (pinfunction "CA3_23") (pintype "bidirectional"))
    )
    (net (code "5") (name "/CA4") (class "Default")
      (node (ref "LED16") (pin "+") (pinfunction "+_+") (pintype "passive"))
      (node (ref "LED2") (pin "+") (pinfunction "+_+") (pintype "passive"))
      (node (ref "LED22") (pin "-") (pinfunction "-_-") (pintype "passive"))
      (node (ref "LED23") (pin "-") (pinfunction "-_-") (pintype "passive"))
      (node (ref "LED24") (pin "-") (pinfunction "-_-") (pintype "passive"))
      (node (ref "LED25") (pin "-") (pinfunction "-_-") (pintype "passive"))
      (node (ref "LED26") (pin "-") (pinfunction "-_-") (pintype "passive"))
      (node (ref "LED27") (pin "-") (pinfunction "-_-") (pintype "passive"))
      (node (ref "LED28") (pin "-") (pinfunction "-_-") (pintype "passive"))
      (node (ref "LED31") (pin "+") (pinfunction "+_+") (pintype "passive"))
      (node (ref "LED38") (pin "+") (pinfunction "+_+") (pintype "passive"))
      (node (ref "LED45") (pin "+") (pinfunction "+_+") (pintype "passive"))
      (node (ref "LED52") (pin "+") (pinfunction "+_+") (pintype "passive"))
      (node (ref "LED9") (pin "+") (pinfunction "+_+") (pintype "passive"))
      (node (ref "U1") (pin "24") (pinfunction "CA4_24") (pintype "bidirectional"))
    )
    (net (code "6") (name "/CA5") (class "Default")
      (node (ref "LED10") (pin "+") (pinfunction "+_+") (pintype "passive"))
      (node (ref "LED17") (pin "+") (pinfunction "+_+") (pintype "passive"))
      (node (ref "LED24") (pin "+") (pinfunction "+_+") (pintype "passive"))
      (node (ref "LED29") (pin "-") (pinfunction "-_-") (pintype "passive"))
      (node (ref "LED3") (pin "+") (pinfunction "+_+") (pintype "passive"))
      (node (ref "LED30") (pin "-") (pinfunction "-_-") (pintype "passive"))
      (node (ref "LED31") (pin "-") (pinfunction "-_-") (pintype "passive"))
      (node (ref "LED32") (pin "-") (pinfunction "-_-") (pintype "passive"))
      (node (ref "LED33") (pin "-") (pinfunction "-_-") (pintype "passive"))
      (node (ref "LED34") (pin "-") (pinfunction "-_-") (pintype "passive"))
      (node (ref "LED35") (pin "-") (pinfunction "-_-") (pintype "passive"))
      (node (ref "LED39") (pin "+") (pinfunction "+_+") (pintype "passive"))
      (node (ref "LED46") (pin "+") (pinfunction "+_+") (pintype "passive"))
      (node (ref "LED53") (pin "+") (pinfunction "+_+") (pintype "passive"))
      (node (ref "U1") (pin "25") (pinfunction "CA5_25") (pintype "bidirectional"))
    )
    (net (code "7") (name "/CA6") (class "Default")
      (node (ref "LED11") (pin "+") (pinfunction "+_+") (pintype "passive"))
      (node (ref "LED18") (pin "+") (pinfunction "+_+") (pintype "passive"))
      (node (ref "LED25") (pin "+") (pinfunction "+_+") (pintype "passive"))
      (node (ref "LED32") (pin "+") (pinfunction "+_+") (pintype "passive"))
      (node (ref "LED36") (pin "-") (pinfunction "-_-") (pintype "passive"))
      (node (ref "LED37") (pin "-") (pinfunction "-_-") (pintype "passive"))
      (node (ref "LED38") (pin "-") (pinfunction "-_-") (pintype "passive"))
      (node (ref "LED39") (pin "-") (pinfunction "-_-") (pintype "passive"))
      (node (ref "LED4") (pin "+") (pinfunction "+_+") (pintype "passive"))
      (node (ref "LED40") (pin "-") (pinfunction "-_-") (pintype "passive"))
      (node (ref "LED41") (pin "-") (pinfunction "-_-") (pintype "passive"))
      (node (ref "LED42") (pin "-") (pinfunction "-_-") (pintype "passive"))
      (node (ref "LED47") (pin "+") (pinfunction "+_+") (pintype "passive"))
      (node (ref "LED54") (pin "+") (pinfunction "+_+") (pintype "passive"))
      (node (ref "U1") (pin "26") (pinfunction "CA6_26") (pintype "bidirectional"))
    )
    (net (code "8") (name "/CA7") (class "Default")
      (node (ref "LED12") (pin "+") (pinfunction "+_+") (pintype "passive"))
      (node (ref "LED19") (pin "+") (pinfunction "+_+") (pintype "passive"))
      (node (ref "LED26") (pin "+") (pinfunction "+_+") (pintype "passive"))
      (node (ref "LED33") (pin "+") (pinfunction "+_+") (pintype "passive"))
      (node (ref "LED40") (pin "+") (pinfunction "+_+") (pintype "passive"))
      (node (ref "LED43") (pin "-") (pinfunction "-_-") (pintype "passive"))
      (node (ref "LED44") (pin "-") (pinfunction "-_-") (pintype "passive"))
      (node (ref "LED45") (pin "-") (pinfunction "-_-") (pintype "passive"))
      (node (ref "LED46") (pin "-") (pinfunction "-_-") (pintype "passive"))
      (node (ref "LED47") (pin "-") (pinfunction "-_-") (pintype "passive"))
      (node (ref "LED48") (pin "-") (pinfunction "-_-") (pintype "passive"))
      (node (ref "LED49") (pin "-") (pinfunction "-_-") (pintype "passive"))
      (node (ref "LED5") (pin "+") (pinfunction "+_+") (pintype "passive"))
      (node (ref "LED55") (pin "+") (pinfunction "+_+") (pintype "passive"))
      (node (ref "U1") (pin "27") (pinfunction "CA7_27") (pintype "bidirectional"))
    )
    (net (code "9") (name "/CA8") (class "Default")
      (node (ref "LED13") (pin "+") (pinfunction "+_+") (pintype "passive"))
      (node (ref "LED20") (pin "+") (pinfunction "+_+") (pintype "passive"))
      (node (ref "LED27") (pin "+") (pinfunction "+_+") (pintype "passive"))
      (node (ref "LED34") (pin "+") (pinfunction "+_+") (pintype "passive"))
      (node (ref "LED41") (pin "+") (pinfunction "+_+") (pintype "passive"))
      (node (ref "LED48") (pin "+") (pinfunction "+_+") (pintype "passive"))
      (node (ref "LED50") (pin "-") (pinfunction "-_-") (pintype "passive"))
      (node (ref "LED51") (pin "-") (pinfunction "-_-") (pintype "passive"))
      (node (ref "LED52") (pin "-") (pinfunction "-_-") (pintype "passive"))
      (node (ref "LED53") (pin "-") (pinfunction "-_-") (pintype "passive"))
      (node (ref "LED54") (pin "-") (pinfunction "-_-") (pintype "passive"))
      (node (ref "LED55") (pin "-") (pinfunction "-_-") (pintype "passive"))
      (node (ref "LED56") (pin "-") (pinfunction "-_-") (pintype "passive"))
      (node (ref "LED6") (pin "+") (pinfunction "+_+") (pintype "passive"))
      (node (ref "U1") (pin "28") (pinfunction "CA8_28") (pintype "bidirectional"))
    )
    (net (code "10") (name "/CA9") (class "Default")
      (node (ref "LED14") (pin "+") (pinfunction "+_+") (pintype "passive"))
      (node (ref "LED21") (pin "+") (pinfunction "+_+") (pintype "passive"))
      (node (ref "LED28") (pin "+") (pinfunction "+_+") (pintype "passive"))
      (node (ref "LED35") (pin "+") (pinfunction "+_+") (pintype "passive"))
      (node (ref "LED42") (pin "+") (pinfunction "+_+") (pintype "passive"))
      (node (ref "LED49") (pin "+") (pinfunction "+_+") (pintype "passive"))
      (node (ref "LED56") (pin "+") (pinfunction "+_+") (pintype "passive"))
      (node (ref "LED7") (pin "+") (pinfunction "+_+") (pintype "passive"))
      (node (ref "U1") (pin "1") (pinfunction "CA9_1") (pintype "bidirectional"))
    )
    (net (code "11") (name "/CB1") (class "Default")
      (node (ref "LED57") (pin "+") (pinfunction "+_+") (pintype "passive"))
      (node (ref "LED64") (pin "+") (pinfunction "+_+") (pintype "passive"))
      (node (ref "LED71") (pin "+") (pinfunction "+_+") (pintype "passive"))
      (node (ref "LED78") (pin "+") (pinfunction "+_+") (pintype "passive"))
      (node (ref "LED85") (pin "+") (pinfunction "+_+") (pintype "passive"))
      (node (ref "LED92") (pin "+") (pinfunction "+_+") (pintype "passive"))
      (node (ref "LED99") (pin "+") (pinfunction "+_+") (pintype "passive"))
      (node (ref "U1") (pin "7") (pinfunction "CB1_7") (pintype "bidirectional"))
    )
    (net (code "12") (name "/CB2") (class "Default")
      (node (ref "LED100") (pin "-") (pinfunction "-_-") (pintype "passive"))
      (node (ref "LED101") (pin "-") (pinfunction "-_-") (pintype "passive"))
      (node (ref "LED102") (pin "-") (pinfunction "-_-") (pintype "passive"))
      (node (ref "LED103") (pin "-") (pinfunction "-_-") (pintype "passive"))
      (node (ref "LED104") (pin "-") (pinfunction "-_-") (pintype "passive"))
      (node (ref "LED105") (pin "-") (pinfunction "-_-") (pintype "passive"))
      (node (ref "LED58") (pin "+") (pinfunction "+_+") (pintype "passive"))
      (node (ref "LED65") (pin "+") (pinfunction "+_+") (pintype "passive"))
      (node (ref "LED72") (pin "+") (pinfunction "+_+") (pintype "passive"))
      (node (ref "LED79") (pin "+") (pinfunction "+_+") (pintype "passive"))
      (node (ref "LED86") (pin "+") (pinfunction "+_+") (pintype "passive"))
      (node (ref "LED93") (pin "+") (pinfunction "+_+") (pintype "passive"))
      (node (ref "LED99") (pin "-") (pinfunction "-_-") (pintype "passive"))
      (node (ref "U1") (pin "8") (pinfunction "CB2_8") (pintype "bidirectional"))
    )
    (net (code "13") (name "/CB3") (class "Default")
      (node (ref "LED100") (pin "+") (pinfunction "+_+") (pintype "passive"))
      (node (ref "LED59") (pin "+") (pinfunction "+_+") (pintype "passive"))
      (node (ref "LED66") (pin "+") (pinfunction "+_+") (pintype "passive"))
      (node (ref "LED73") (pin "+") (pinfunction "+_+") (pintype "passive"))
      (node (ref "LED80") (pin "+") (pinfunction "+_+") (pintype "passive"))
      (node (ref "LED87") (pin "+") (pinfunction "+_+") (pintype "passive"))
      (node (ref "LED92") (pin "-") (pinfunction "-_-") (pintype "passive"))
      (node (ref "LED93") (pin "-") (pinfunction "-_-") (pintype "passive"))
      (node (ref "LED94") (pin "-") (pinfunction "-_-") (pintype "passive"))
      (node (ref "LED95") (pin "-") (pinfunction "-_-") (pintype "passive"))
      (node (ref "LED96") (pin "-") (pinfunction "-_-") (pintype "passive"))
      (node (ref "LED97") (pin "-") (pinfunction "-_-") (pintype "passive"))
      (node (ref "LED98") (pin "-") (pinfunction "-_-") (pintype "passive"))
      (node (ref "U1") (pin "9") (pinfunction "CB3_9") (pintype "bidirectional"))
    )
    (net (code "14") (name "/CB4") (class "Default")
      (node (ref "LED101") (pin "+") (pinfunction "+_+") (pintype "passive"))
      (node (ref "LED60") (pin "+") (pinfunction "+_+") (pintype "passive"))
      (node (ref "LED67") (pin "+") (pinfunction "+_+") (pintype "passive"))
      (node (ref "LED74") (pin "+") (pinfunction "+_+") (pintype "passive"))
      (node (ref "LED81") (pin "+") (pinfunction "+_+") (pintype "passive"))
      (node (ref "LED85") (pin "-") (pinfunction "-_-") (pintype "passive"))
      (node (ref "LED86") (pin "-") (pinfunction "-_-") (pintype "passive"))
      (node (ref "LED87") (pin "-") (pinfunction "-_-") (pintype "passive"))
      (node (ref "LED88") (pin "-") (pinfunction "-_-") (pintype "passive"))
      (node (ref "LED89") (pin "-") (pinfunction "-_-") (pintype "passive"))
      (node (ref "LED90") (pin "-") (pinfunction "-_-") (pintype "passive"))
      (node (ref "LED91") (pin "-") (pinfunction "-_-") (pintype "passive"))
      (node (ref "LED94") (pin "+") (pinfunction "+_+") (pintype "passive"))
      (node (ref "U1") (pin "10") (pinfunction "CB4_10") (pintype "bidirectional"))
    )
    (net (code "15") (name "/CB5") (class "Default")
      (node (ref "LED102") (pin "+") (pinfunction "+_+") (pintype "passive"))
      (node (ref "LED61") (pin "+") (pinfunction "+_+") (pintype "passive"))
      (node (ref "LED68") (pin "+") (pinfunction "+_+") (pintype "passive"))
      (node (ref "LED75") (pin "+") (pinfunction "+_+") (pintype "passive"))
      (node (ref "LED78") (pin "-") (pinfunction "-_-") (pintype "passive"))
      (node (ref "LED79") (pin "-") (pinfunction "-_-") (pintype "passive"))
      (node (ref "LED80") (pin "-") (pinfunction "-_-") (pintype "passive"))
      (node (ref "LED81") (pin "-") (pinfunction "-_-") (pintype "passive"))
      (node (ref "LED82") (pin "-") (pinfunction "-_-") (pintype "passive"))
      (node (ref "LED83") (pin "-") (pinfunction "-_-") (pintype "passive"))
      (node (ref "LED84") (pin "-") (pinfunction "-_-") (pintype "passive"))
      (node (ref "LED88") (pin "+") (pinfunction "+_+") (pintype "passive"))
      (node (ref "LED95") (pin "+") (pinfunction "+_+") (pintype "passive"))
      (node (ref "U1") (pin "11") (pinfunction "CB5_11") (pintype "bidirectional"))
    )
    (net (code "16") (name "/CB6") (class "Default")
      (node (ref "LED103") (pin "+") (pinfunction "+_+") (pintype "passive"))
      (node (ref "LED62") (pin "+") (pinfunction "+_+") (pintype "passive"))
      (node (ref "LED69") (pin "+") (pinfunction "+_+") (pintype "passive"))
      (node (ref "LED71") (pin "-") (pinfunction "-_-") (pintype "passive"))
      (node (ref "LED72") (pin "-") (pinfunction "-_-") (pintype "passive"))
      (node (ref "LED73") (pin "-") (pinfunction "-_-") (pintype "passive"))
      (node (ref "LED74") (pin "-") (pinfunction "-_-") (pintype "passive"))
      (node (ref "LED75") (pin "-") (pinfunction "-_-") (pintype "passive"))
      (node (ref "LED76") (pin "-") (pinfunction "-_-") (pintype "passive"))
      (node (ref "LED77") (pin "-") (pinfunction "-_-") (pintype "passive"))
      (node (ref "LED82") (pin "+") (pinfunction "+_+") (pintype "passive"))
      (node (ref "LED89") (pin "+") (pinfunction "+_+") (pintype "passive"))
      (node (ref "LED96") (pin "+") (pinfunction "+_+") (pintype "passive"))
      (node (ref "U1") (pin "12") (pinfunction "CB6_12") (pintype "bidirectional"))
    )
    (net (code "17") (name "/CB7") (class "Default")
      (node (ref "LED104") (pin "+") (pinfunction "+_+") (pintype "passive"))
      (node (ref "LED63") (pin "+") (pinfunction "+_+") (pintype "passive"))
      (node (ref "LED64") (pin "-") (pinfunction "-_-") (pintype "passive"))
      (node (ref "LED65") (pin "-") (pinfunction "-_-") (pintype "passive"))
      (node (ref "LED66") (pin "-") (pinfunction "-_-") (pintype "passive"))
      (node (ref "LED67") (pin "-") (pinfunction "-_-") (pintype "passive"))
      (node (ref "LED68") (pin "-") (pinfunction "-_-") (pintype "passive"))
      (node (ref "LED69") (pin "-") (pinfunction "-_-") (pintype "passive"))
      (node (ref "LED70") (pin "-") (pinfunction "-_-") (pintype "passive"))
      (node (ref "LED76") (pin "+") (pinfunction "+_+") (pintype "passive"))
      (node (ref "LED83") (pin "+") (pinfunction "+_+") (pintype "passive"))
      (node (ref "LED90") (pin "+") (pinfunction "+_+") (pintype "passive"))
      (node (ref "LED97") (pin "+") (pinfunction "+_+") (pintype "passive"))
      (node (ref "U1") (pin "13") (pinfunction "CB7_13") (pintype "bidirectional"))
    )
    (net (code "18") (name "/CB8") (class "Default")
      (node (ref "LED105") (pin "+") (pinfunction "+_+") (pintype "passive"))
      (node (ref "LED57") (pin "-") (pinfunction "-_-") (pintype "passive"))
      (node (ref "LED58") (pin "-") (pinfunction "-_-") (pintype "passive"))
      (node (ref "LED59") (pin "-") (pinfunction "-_-") (pintype "passive"))
      (node (ref "LED60") (pin "-") (pinfunction "-_-") (pintype "passive"))
      (node (ref "LED61") (pin "-") (pinfunction "-_-") (pintype "passive"))
      (node (ref "LED62") (pin "-") (pinfunction "-_-") (pintype "passive"))
      (node (ref "LED63") (pin "-") (pinfunction "-_-") (pintype "passive"))
      (node (ref "LED70") (pin "+") (pinfunction "+_+") (pintype "passive"))
      (node (ref "LED77") (pin "+") (pinfunction "+_+") (pintype "passive"))
      (node (ref "LED84") (pin "+") (pinfunction "+_+") (pintype "passive"))
      (node (ref "LED91") (pin "+") (pinfunction "+_+") (pintype "passive"))
      (node (ref "LED98") (pin "+") (pinfunction "+_+") (pintype "passive"))
      (node (ref "U1") (pin "14") (pinfunction "CB8_14") (pintype "bidirectional"))
    )
    (net (code "19") (name "/DISPLAY_POWER") (class "Default")
      (node (ref "C2") (pin "1") (pinfunction "1_1") (pintype "passive"))
      (node (ref "C3") (pin "1") (pinfunction "1_1") (pintype "passive"))
      (node (ref "C7") (pin "1") (pinfunction "1_1") (pintype "passive"))
      (node (ref "J2") (pin "2") (pinfunction "2_2") (pintype "power_in"))
      (node (ref "R3") (pin "1") (pinfunction "1_1") (pintype "passive"))
      (node (ref "R4") (pin "2") (pinfunction "2_2") (pintype "passive"))
      (node (ref "U1") (pin "2") (pinfunction "VCC_2") (pintype "power_in"))
    )
    (net (code "20") (name "GND") (class "Default")
      (node (ref "C1") (pin "2") (pinfunction "2_2") (pintype "passive"))
      (node (ref "C2") (pin "2") (pinfunction "2_2") (pintype "passive"))
      (node (ref "C3") (pin "2") (pinfunction "2_2") (pintype "passive"))
      (node (ref "C7") (pin "2") (pinfunction "2_2") (pintype "passive"))
      (node (ref "J2") (pin "1") (pinfunction "1_1") (pintype "power_in"))
      (node (ref "R1") (pin "2") (pinfunction "2_2") (pintype "passive"))
      (node (ref "R2") (pin "2") (pinfunction "2_2") (pintype "passive"))
      (node (ref "U1") (pin "5") (pinfunction "GND_5") (pintype "power_in"))
      (node (ref "U1") (pin "THERMAL") (pinfunction "GND_THERMAL") (pintype "power_in"))
    )
    (net (code "21") (name "Net-(U1-C_FILT)") (class "Default")
      (node (ref "C1") (pin "1") (pinfunction "1_1") (pintype "passive"))
      (node (ref "U1") (pin "16") (pinfunction "C_FILT_16") (pintype "bidirectional"))
    )
    (net (code "22") (name "Net-(U1-INTB)") (class "Default")
      (node (ref "R4") (pin "1") (pinfunction "1_1") (pintype "passive"))
      (node (ref "U1") (pin "4") (pinfunction "INTB_4") (pintype "output"))
    )
    (net (code "23") (name "Net-(U1-R_EXT)") (class "Default")
      (node (ref "R2") (pin "1") (pinfunction "1_1") (pintype "passive"))
      (node (ref "U1") (pin "6") (pinfunction "R_EXT_6") (pintype "bidirectional"))
    )
    (net (code "24") (name "Net-(U1-SHUTDOWN)") (class "Default")
      (node (ref "R3") (pin "2") (pinfunction "2_2") (pintype "passive"))
      (node (ref "U1") (pin "3") (pinfunction "SHUTDOWN_3") (pintype "input"))
    )
    (net (code "25") (name "SCL") (class "Default")
      (node (ref "J2") (pin "4") (pinfunction "4_4") (pintype "passive"))
      (node (ref "U1") (pin "20") (pinfunction "SCL_20") (pintype "bidirectional"))
    )
    (net (code "26") (name "SDA") (class "Default")
      (node (ref "J2") (pin "3") (pinfunction "3_3") (pintype "passive"))
      (node (ref "U1") (pin "19") (pinfunction "SDA_19") (pintype "bidirectional"))
    )
    (net (code "27") (name "unconnected-(U1-AUDIOIN-Pad17)") (class "Default")
      (node (ref "U1") (pin "17") (pinfunction "AUDIOIN_17") (pintype "input"))
    )
    (net (code "28") (name "unconnected-(U1-CB9-Pad15)") (class "Default")
      (node (ref "U1") (pin "15") (pinfunction "CB9_15") (pintype "bidirectional"))
    )
  )
)
